# CentralBoard.net
KiCad netlist of a schematic drawn in EAGLE
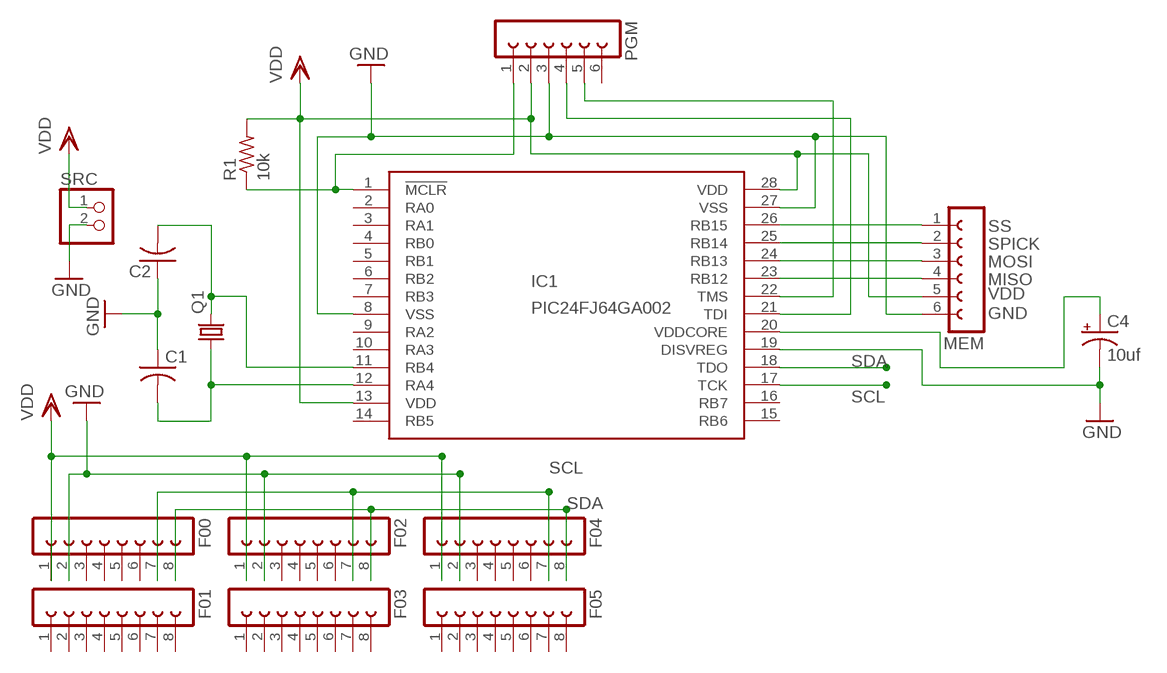
[diagram p0: schematic, sheet 1]

(export (version "E")
  (design (tool "Eeschema 10.0.6"))
  (components
    (comp (ref "C1")
      (value "C-US025-030X050")
      (footprint "eagle-import:C025-030X050")
      (libsource (lib "eagle-import") (part "C-US025-030X050"))
    )
    (comp (ref "C2")
      (value "C-US025-030X050")
      (footprint "eagle-import:C025-030X050")
      (libsource (lib "eagle-import") (part "C-US025-030X050"))
    )
    (comp (ref "C4")
      (value "10uf")
      (footprint "eagle-import:E5-8,5")
      (libsource (lib "eagle-import") (part "CPOL-USE5-8.5"))
    )
    (comp (ref "F00")
      (value "FE08-1")
      (footprint "eagle-import:FE08")
      (libsource (lib "eagle-import") (part "FE08-1"))
    )
    (comp (ref "F01")
      (value "FE08-1")
      (footprint "eagle-import:FE08")
      (libsource (lib "eagle-import") (part "FE08-1"))
    )
    (comp (ref "F02")
      (value "FE08-1")
      (footprint "eagle-import:FE08")
      (libsource (lib "eagle-import") (part "FE08-1"))
    )
    (comp (ref "F03")
      (value "FE08-1")
      (footprint "eagle-import:FE08")
      (libsource (lib "eagle-import") (part "FE08-1"))
    )
    (comp (ref "F04")
      (value "FE08-1")
      (footprint "eagle-import:FE08")
      (libsource (lib "eagle-import") (part "FE08-1"))
    )
    (comp (ref "F05")
      (value "FE08-1")
      (footprint "eagle-import:FE08")
      (libsource (lib "eagle-import") (part "FE08-1"))
    )
    (comp (ref "IC1")
      (value "PIC24FJ64GA002")
      (footprint "eagle-import:DIL28-3")
      (fields (field (name "MPN") "PIC24FJ64GA002-I/SP"))
      (libsource (lib "eagle-import") (part "PIC24FJ64GA002"))
    )
    (comp (ref "MEM")
      (value "FE06-1")
      (footprint "eagle-import:FE06")
      (libsource (lib "eagle-import") (part "FE06-1"))
    )
    (comp (ref "PGM")
      (value "FE06-1")
      (footprint "eagle-import:FE06")
      (libsource (lib "eagle-import") (part "FE06-1"))
    )
    (comp (ref "Q1")
      (value "CRYSTALTC26V")
      (footprint "eagle-import:TC26V")
      (libsource (lib "eagle-import") (part "CRYSTALTC26V"))
    )
    (comp (ref "R1")
      (value "10k")
      (footprint "eagle-import:0204_7")
      (libsource (lib "eagle-import") (part "R-US_0204/7"))
    )
    (comp (ref "SRC")
      (value "PINHD-1X2")
      (footprint "eagle-import:1X02")
      (libsource (lib "eagle-import") (part "PINHD-1X2"))
    )
  )
  (nets
    (net (code "1") (name "/MISO") (class "Default")
      (node (ref "IC1") (pin "23") (pinfunction "RB12_23") (pintype "bidirectional"))
      (node (ref "MEM") (pin "4") (pinfunction "4_4") (pintype "passive"))
    )
    (net (code "2") (name "/MOSI") (class "Default")
      (node (ref "IC1") (pin "24") (pinfunction "RB13_24") (pintype "bidirectional"))
      (node (ref "MEM") (pin "3") (pinfunction "3_3") (pintype "passive"))
    )
    (net (code "3") (name "/SCL") (class "Default")
      (node (ref "F00") (pin "7") (pinfunction "7_7") (pintype "passive"))
      (node (ref "F02") (pin "7") (pinfunction "7_7") (pintype "passive"))
      (node (ref "F04") (pin "7") (pinfunction "7_7") (pintype "passive"))
      (node (ref "IC1") (pin "17") (pinfunction "TCK_17") (pintype "input"))
    )
    (net (code "4") (name "/SDA") (class "Default")
      (node (ref "F00") (pin "8") (pinfunction "8_8") (pintype "passive"))
      (node (ref "F02") (pin "8") (pinfunction "8_8") (pintype "passive"))
      (node (ref "F04") (pin "8") (pinfunction "8_8") (pintype "passive"))
      (node (ref "IC1") (pin "18") (pinfunction "TDO_18") (pintype "output"))
    )
    (net (code "5") (name "/SPICK") (class "Default")
      (node (ref "IC1") (pin "25") (pinfunction "RB14_25") (pintype "bidirectional"))
      (node (ref "MEM") (pin "2") (pinfunction "2_2") (pintype "passive"))
    )
    (net (code "6") (name "/SS") (class "Default")
      (node (ref "IC1") (pin "26") (pinfunction "RB15_26") (pintype "bidirectional"))
      (node (ref "MEM") (pin "1") (pinfunction "1_1") (pintype "passive"))
    )
    (net (code "7") (name "GND") (class "Default")
      (node (ref "C1") (pin "1") (pinfunction "1_1") (pintype "passive"))
      (node (ref "C2") (pin "1") (pinfunction "1_1") (pintype "passive"))
      (node (ref "C4") (pin "-") (pinfunction "-_-") (pintype "passive"))
      (node (ref "F00") (pin "2") (pinfunction "2_2") (pintype "passive"))
      (node (ref "F02") (pin "2") (pinfunction "2_2") (pintype "passive"))
      (node (ref "F04") (pin "2") (pinfunction "2_2") (pintype "passive"))
      (node (ref "IC1") (pin "19") (pinfunction "DISVREG_19") (pintype "passive"))
      (node (ref "IC1") (pin "27") (pinfunction "VSS_27") (pintype "power_in"))
      (node (ref "IC1") (pin "8") (pinfunction "VSS_8") (pintype "power_in"))
      (node (ref "MEM") (pin "6") (pinfunction "6_6") (pintype "passive"))
      (node (ref "PGM") (pin "3") (pinfunction "3_3") (pintype "passive"))
      (node (ref "SRC") (pin "2") (pinfunction "2_2") (pintype "passive"))
    )
    (net (code "8") (name "Net-(IC1-RA4)") (class "Default")
      (node (ref "C1") (pin "2") (pinfunction "2_2") (pintype "passive"))
      (node (ref "IC1") (pin "12") (pinfunction "RA4_12") (pintype "bidirectional"))
      (node (ref "Q1") (pin "1") (pinfunction "1_1") (pintype "passive"))
    )
    (net (code "9") (name "Net-(IC1-RB4)") (class "Default")
      (node (ref "C2") (pin "2") (pinfunction "2_2") (pintype "passive"))
      (node (ref "IC1") (pin "11") (pinfunction "RB4_11") (pintype "bidirectional"))
      (node (ref "Q1") (pin "2") (pinfunction "2_2") (pintype "passive"))
    )
    (net (code "10") (name "Net-(IC1-TDI)") (class "Default")
      (node (ref "IC1") (pin "21") (pinfunction "TDI_21") (pintype "input"))
      (node (ref "PGM") (pin "4") (pinfunction "4_4") (pintype "passive"))
    )
    (net (code "11") (name "Net-(IC1-TMS)") (class "Default")
      (node (ref "IC1") (pin "22") (pinfunction "TMS_22") (pintype "input"))
      (node (ref "PGM") (pin "5") (pinfunction "5_5") (pintype "passive"))
    )
    (net (code "12") (name "Net-(IC1-VDDCORE)") (class "Default")
      (node (ref "C4") (pin "+") (pinfunction "+_+") (pintype "passive"))
      (node (ref "IC1") (pin "20") (pinfunction "VDDCORE_20") (pintype "power_in"))
    )
    (net (code "13") (name "Net-(IC1-~{MCLR})") (class "Default")
      (node (ref "IC1") (pin "1") (pinfunction "~{MCLR}_1") (pintype "bidirectional"))
      (node (ref "PGM") (pin "1") (pinfunction "1_1") (pintype "passive"))
      (node (ref "R1") (pin "1") (pinfunction "1_1") (pintype "passive"))
    )
    (net (code "14") (name "VDD") (class "Default")
      (node (ref "F00") (pin "1") (pinfunction "1_1") (pintype "passive"))
      (node (ref "F02") (pin "1") (pinfunction "1_1") (pintype "passive"))
      (node (ref "F04") (pin "1") (pinfunction "1_1") (pintype "passive"))
      (node (ref "IC1") (pin "13") (pinfunction "VDD_13") (pintype "power_in"))
      (node (ref "IC1") (pin "28") (pinfunction "VDD_28") (pintype "power_in"))
      (node (ref "MEM") (pin "5") (pinfunction "5_5") (pintype "passive"))
      (node (ref "PGM") (pin "2") (pinfunction "2_2") (pintype "passive"))
      (node (ref "R1") (pin "2") (pinfunction "2_2") (pintype "passive"))
      (node (ref "SRC") (pin "1") (pinfunction "1_1") (pintype "passive"))
    )
    (net (code "15") (name "unconnected-(F00-Pad3)") (class "Default")
      (node (ref "F00") (pin "3") (pinfunction "3_3") (pintype "passive"))
    )
    (net (code "16") (name "unconnected-(F00-Pad4)") (class "Default")
      (node (ref "F00") (pin "4") (pinfunction "4_4") (pintype "passive"))
    )
    (net (code "17") (name "unconnected-(F00-Pad5)") (class "Default")
      (node (ref "F00") (pin "5") (pinfunction "5_5") (pintype "passive"))
    )
    (net (code "18") (name "unconnected-(F00-Pad6)") (class "Default")
      (node (ref "F00") (pin "6") (pinfunction "6_6") (pintype "passive"))
    )
    (net (code "19") (name "unconnected-(F01-Pad1)") (class "Default")
      (node (ref "F01") (pin "1") (pinfunction "1_1") (pintype "passive"))
    )
    (net (code "20") (name "unconnected-(F01-Pad2)") (class "Default")
      (node (ref "F01") (pin "2") (pinfunction "2_2") (pintype "passive"))
    )
    (net (code "21") (name "unconnected-(F01-Pad3)") (class "Default")
      (node (ref "F01") (pin "3") (pinfunction "3_3") (pintype "passive"))
    )
    (net (code "22") (name "unconnected-(F01-Pad4)") (class "Default")
      (node (ref "F01") (pin "4") (pinfunction "4_4") (pintype "passive"))
    )
    (net (code "23") (name "unconnected-(F01-Pad5)") (class "Default")
      (node (ref "F01") (pin "5") (pinfunction "5_5") (pintype "passive"))
    )
    (net (code "24") (name "unconnected-(F01-Pad6)") (class "Default")
      (node (ref "F01") (pin "6") (pinfunction "6_6") (pintype "passive"))
    )
    (net (code "25") (name "unconnected-(F01-Pad7)") (class "Default")
      (node (ref "F01") (pin "7") (pinfunction "7_7") (pintype "passive"))
    )
    (net (code "26") (name "unconnected-(F01-Pad8)") (class "Default")
      (node (ref "F01") (pin "8") (pinfunction "8_8") (pintype "passive"))
    )
    (net (code "27") (name "unconnected-(F02-Pad3)") (class "Default")
      (node (ref "F02") (pin "3") (pinfunction "3_3") (pintype "passive"))
    )
    (net (code "28") (name "unconnected-(F02-Pad4)") (class "Default")
      (node (ref "F02") (pin "4") (pinfunction "4_4") (pintype "passive"))
    )
    (net (code "29") (name "unconnected-(F02-Pad5)") (class "Default")
      (node (ref "F02") (pin "5") (pinfunction "5_5") (pintype "passive"))
    )
    (net (code "30") (name "unconnected-(F02-Pad6)") (class "Default")
      (node (ref "F02") (pin "6") (pinfunction "6_6") (pintype "passive"))
    )
    (net (code "31") (name "unconnected-(F03-Pad1)") (class "Default")
      (node (ref "F03") (pin "1") (pinfunction "1_1") (pintype "passive"))
    )
    (net (code "32") (name "unconnected-(F03-Pad2)") (class "Default")
      (node (ref "F03") (pin "2") (pinfunction "2_2") (pintype "passive"))
    )
    (net (code "33") (name "unconnected-(F03-Pad3)") (class "Default")
      (node (ref "F03") (pin "3") (pinfunction "3_3") (pintype "passive"))
    )
    (net (code "34") (name "unconnected-(F03-Pad4)") (class "Default")
      (node (ref "F03") (pin "4") (pinfunction "4_4") (pintype "passive"))
    )
    (net (code "35") (name "unconnected-(F03-Pad5)") (class "Default")
      (node (ref "F03") (pin "5") (pinfunction "5_5") (pintype "passive"))
    )
    (net (code "36") (name "unconnected-(F03-Pad6)") (class "Default")
      (node (ref "F03") (pin "6") (pinfunction "6_6") (pintype "passive"))
    )
    (net (code "37") (name "unconnected-(F03-Pad7)") (class "Default")
      (node (ref "F03") (pin "7") (pinfunction "7_7") (pintype "passive"))
    )
    (net (code "38") (name "unconnected-(F03-Pad8)") (class "Default")
      (node (ref "F03") (pin "8") (pinfunction "8_8") (pintype "passive"))
    )
    (net (code "39") (name "unconnected-(F04-Pad3)") (class "Default")
      (node (ref "F04") (pin "3") (pinfunction "3_3") (pintype "passive"))
    )
    (net (code "40") (name "unconnected-(F04-Pad4)") (class "Default")
      (node (ref "F04") (pin "4") (pinfunction "4_4") (pintype "passive"))
    )
    (net (code "41") (name "unconnected-(F04-Pad5)") (class "Default")
      (node (ref "F04") (pin "5") (pinfunction "5_5") (pintype "passive"))
    )
    (net (code "42") (name "unconnected-(F04-Pad6)") (class "Default")
      (node (ref "F04") (pin "6") (pinfunction "6_6") (pintype "passive"))
    )
    (net (code "43") (name "unconnected-(F05-Pad1)") (class "Default")
      (node (ref "F05") (pin "1") (pinfunction "1_1") (pintype "passive"))
    )
    (net (code "44") (name "unconnected-(F05-Pad2)") (class "Default")
      (node (ref "F05") (pin "2") (pinfunction "2_2") (pintype "passive"))
    )
    (net (code "45") (name "unconnected-(F05-Pad3)") (class "Default")
      (node (ref "F05") (pin "3") (pinfunction "3_3") (pintype "passive"))
    )
    (net (code "46") (name "unconnected-(F05-Pad4)") (class "Default")
      (node (ref "F05") (pin "4") (pinfunction "4_4") (pintype "passive"))
    )
    (net (code "47") (name "unconnected-(F05-Pad5)") (class "Default")
      (node (ref "F05") (pin "5") (pinfunction "5_5") (pintype "passive"))
    )
    (net (code "48") (name "unconnected-(F05-Pad6)") (class "Default")
      (node (ref "F05") (pin "6") (pinfunction "6_6") (pintype "passive"))
    )
    (net (code "49") (name "unconnected-(F05-Pad7)") (class "Default")
      (node (ref "F05") (pin "7") (pinfunction "7_7") (pintype "passive"))
    )
    (net (code "50") (name "unconnected-(F05-Pad8)") (class "Default")
      (node (ref "F05") (pin "8") (pinfunction "8_8") (pintype "passive"))
    )
    (net (code "51") (name "unconnected-(IC1-RA0-Pad2)") (class "Default")
      (node (ref "IC1") (pin "2") (pinfunction "RA0_2") (pintype "bidirectional"))
    )
    (net (code "52") (name "unconnected-(IC1-RA1-Pad3)") (class "Default")
      (node (ref "IC1") (pin "3") (pinfunction "RA1_3") (pintype "bidirectional"))
    )
    (net (code "53") (name "unconnected-(IC1-RA2-Pad9)") (class "Default")
      (node (ref "IC1") (pin "9") (pinfunction "RA2_9") (pintype "bidirectional"))
    )
    (net (code "54") (name "unconnected-(IC1-RA3-Pad10)") (class "Default")
      (node (ref "IC1") (pin "10") (pinfunction "RA3_10") (pintype "bidirectional"))
    )
    (net (code "55") (name "unconnected-(IC1-RB0-Pad4)") (class "Default")
      (node (ref "IC1") (pin "4") (pinfunction "RB0_4") (pintype "bidirectional"))
    )
    (net (code "56") (name "unconnected-(IC1-RB1-Pad5)") (class "Default")
      (node (ref "IC1") (pin "5") (pinfunction "RB1_5") (pintype "bidirectional"))
    )
    (net (code "57") (name "unconnected-(IC1-RB2-Pad6)") (class "Default")
      (node (ref "IC1") (pin "6") (pinfunction "RB2_6") (pintype "bidirectional"))
    )
    (net (code "58") (name "unconnected-(IC1-RB3-Pad7)") (class "Default")
      (node (ref "IC1") (pin "7") (pinfunction "RB3_7") (pintype "bidirectional"))
    )
    (net (code "59") (name "unconnected-(IC1-RB5-Pad14)") (class "Default")
      (node (ref "IC1") (pin "14") (pinfunction "RB5_14") (pintype "bidirectional"))
    )
    (net (code "60") (name "unconnected-(IC1-RB6-Pad15)") (class "Default")
      (node (ref "IC1") (pin "15") (pinfunction "RB6_15") (pintype "bidirectional"))
    )
    (net (code "61") (name "unconnected-(IC1-RB7-Pad16)") (class "Default")
      (node (ref "IC1") (pin "16") (pinfunction "RB7_16") (pintype "bidirectional"))
    )
    (net (code "62") (name "unconnected-(PGM-Pad6)") (class "Default")
      (node (ref "PGM") (pin "6") (pinfunction "6_6") (pintype "passive"))
    )
  )
)
